# Atom_Multiout_Addon_Comp-Svid.net
KiCad netlist of a schematic drawn in EAGLE
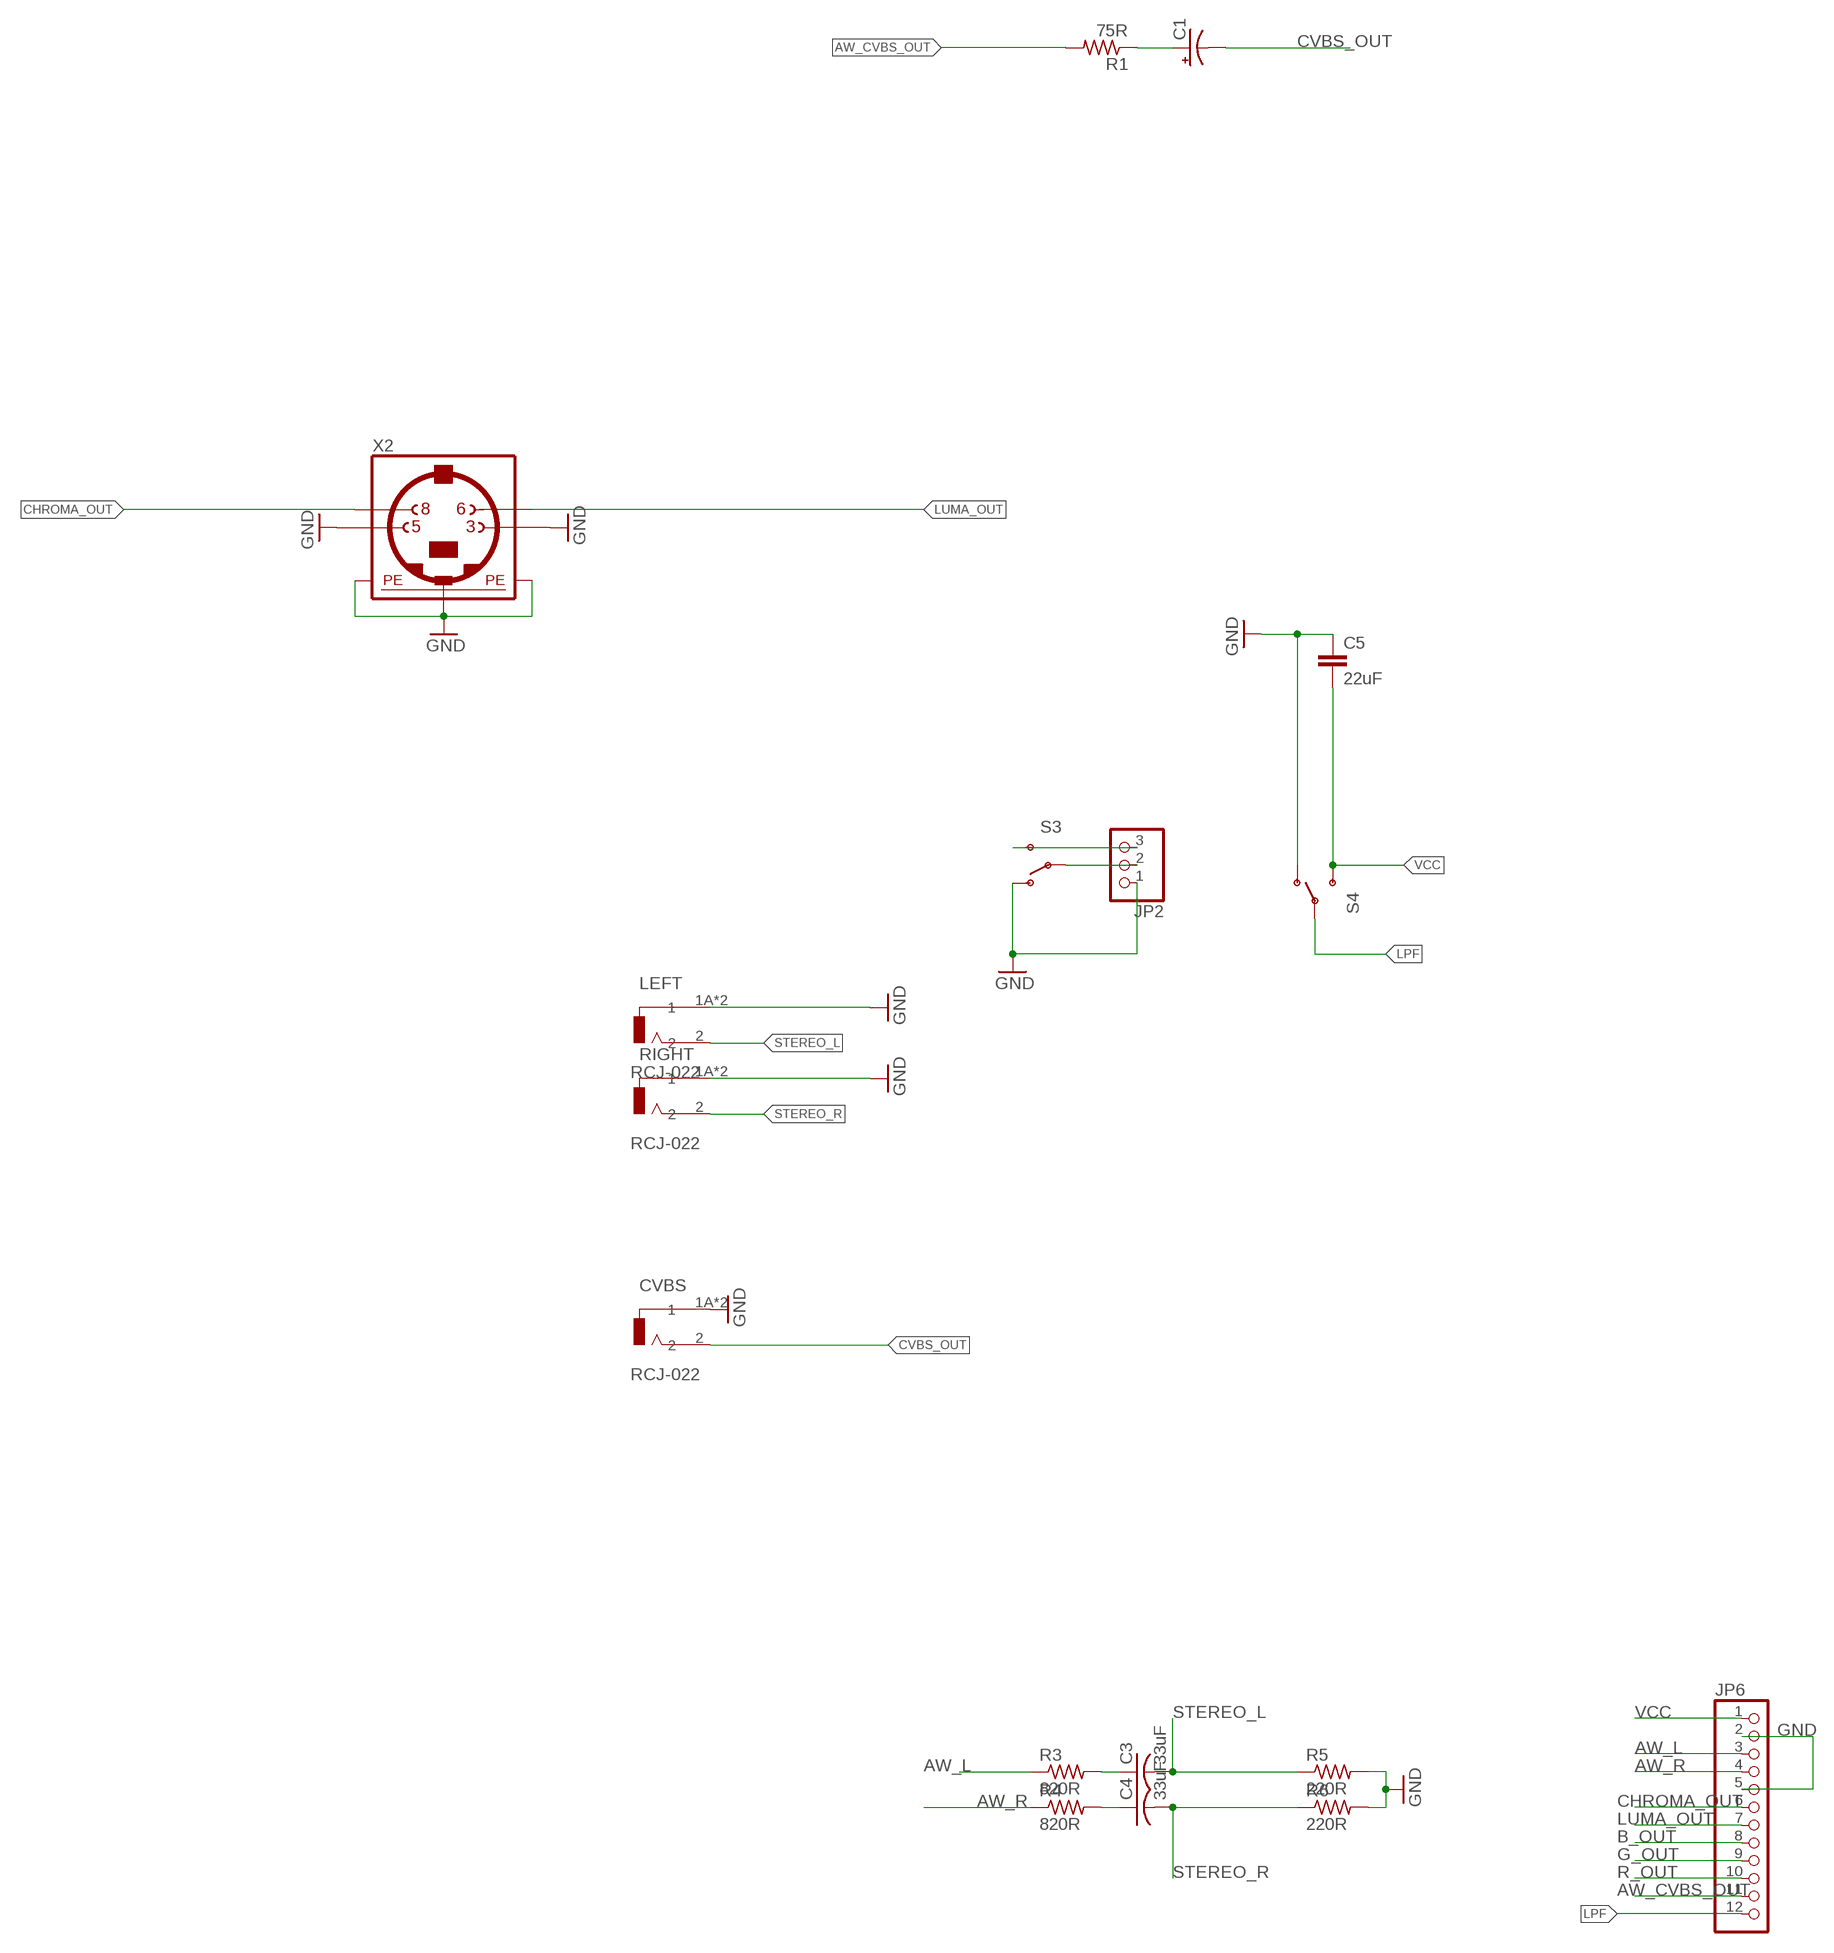
[diagram p0: schematic, sheet 1]

(export (version "E")
  (design (tool "Eeschema 10.0.6"))
  (components
    (comp (ref "C1")
      (value "CPOL-USD/7343-31W")
      (footprint "eagle-import:D_7343-31W")
      (libsource (lib "eagle-import") (part "CPOL-USD/7343-31W"))
    )
    (comp (ref "C3")
      (value "33uF")
      (footprint "eagle-import:C1206K")
      (libsource (lib "eagle-import") (part "C-USC1206K"))
    )
    (comp (ref "C4")
      (value "33uF")
      (footprint "eagle-import:C1206K")
      (libsource (lib "eagle-import") (part "C-USC1206K"))
    )
    (comp (ref "C5")
      (value "22uF")
      (footprint "eagle-import:C0603")
      (libsource (lib "eagle-import") (part "C-EUC0603"))
    )
    (comp (ref "CVBS")
      (value "RCJ-022")
      (footprint "eagle-import:CUI_RCJ-022")
      (fields (field (name "MF") "CUI Devices"))
      (libsource (lib "eagle-import") (part "RCJ-022"))
    )
    (comp (ref "JP2")
      (value "PINHD-1X03_2.54-S")
      (footprint "eagle-import:1X03-S")
      (libsource (lib "eagle-import") (part "PINHD-1X03_2.54-S"))
    )
    (comp (ref "JP6")
      (value "PINHD-1X12_2.54-S")
      (footprint "eagle-import:1X12-S")
      (libsource (lib "eagle-import") (part "PINHD-1X12_2.54-S"))
    )
    (comp (ref "LEFT")
      (value "RCJ-022")
      (footprint "eagle-import:CUI_RCJ-022")
      (fields (field (name "MF") "CUI Devices"))
      (libsource (lib "eagle-import") (part "RCJ-022"))
    )
    (comp (ref "R1")
      (value "75R")
      (footprint "eagle-import:R1206")
      (libsource (lib "eagle-import") (part "R-US_R1206"))
    )
    (comp (ref "R3")
      (value "820R")
      (footprint "eagle-import:R1206")
      (libsource (lib "eagle-import") (part "R-US_R1206"))
    )
    (comp (ref "R4")
      (value "820R")
      (footprint "eagle-import:R1206")
      (libsource (lib "eagle-import") (part "R-US_R1206"))
    )
    (comp (ref "R5")
      (value "220R")
      (footprint "eagle-import:R1206")
      (libsource (lib "eagle-import") (part "R-US_R1206"))
    )
    (comp (ref "R6")
      (value "220R")
      (footprint "eagle-import:R1206")
      (libsource (lib "eagle-import") (part "R-US_R1206"))
    )
    (comp (ref "RIGHT")
      (value "RCJ-022")
      (footprint "eagle-import:CUI_RCJ-022")
      (fields (field (name "MF") "CUI Devices"))
      (libsource (lib "eagle-import") (part "RCJ-022"))
    )
    (comp (ref "S3")
      (value "SWITCH-SPDT-SMD-A")
      (footprint "eagle-import:SWITCH-SPST-SMD-A")
      (libsource (lib "eagle-import") (part "SWITCH-SPDT-SMD-A"))
    )
    (comp (ref "S4")
      (value "SWITCH-SPDT-SMD-A")
      (footprint "eagle-import:SWITCH-SPST-SMD-A")
      (libsource (lib "eagle-import") (part "SWITCH-SPDT-SMD-A"))
    )
    (comp (ref "X2")
      (value "MINI_DIN_4")
      (footprint "eagle-import:M_DIN4")
      (libsource (lib "eagle-import") (part "MINI_DIN_4"))
    )
  )
  (nets
    (net (code "1") (name "/AW_L") (class "Default")
      (node (ref "JP6") (pin "3") (pinfunction "3_3") (pintype "passive"))
      (node (ref "R3") (pin "1") (pinfunction "1_1") (pintype "passive"))
    )
    (net (code "2") (name "/AW_R") (class "Default")
      (node (ref "JP6") (pin "4") (pinfunction "4_4") (pintype "passive"))
      (node (ref "R4") (pin "1") (pinfunction "1_1") (pintype "passive"))
    )
    (net (code "3") (name "/B_OUT") (class "Default")
      (node (ref "JP6") (pin "8") (pinfunction "8_8") (pintype "passive"))
    )
    (net (code "4") (name "/G_OUT") (class "Default")
      (node (ref "JP6") (pin "9") (pinfunction "9_9") (pintype "passive"))
    )
    (net (code "5") (name "/R_OUT") (class "Default")
      (node (ref "JP6") (pin "10") (pinfunction "10_10") (pintype "passive"))
    )
    (net (code "6") (name "AW_CVBS_OUT") (class "Default")
      (node (ref "JP6") (pin "11") (pinfunction "11_11") (pintype "passive"))
      (node (ref "R1") (pin "2") (pinfunction "2_2") (pintype "passive"))
    )
    (net (code "7") (name "CHROMA_OUT") (class "Default")
      (node (ref "JP6") (pin "6") (pinfunction "6_6") (pintype "passive"))
      (node (ref "X2") (pin "8") (pinfunction "8_8") (pintype "passive"))
    )
    (net (code "8") (name "CVBS_OUT") (class "Default")
      (node (ref "C1") (pin "-") (pinfunction "-_-") (pintype "passive"))
      (node (ref "CVBS") (pin "2") (pinfunction "2_2") (pintype "passive"))
    )
    (net (code "9") (name "GND") (class "Default")
      (node (ref "C5") (pin "1") (pinfunction "1_1") (pintype "passive"))
      (node (ref "CVBS") (pin "1A") (pinfunction "1_1A") (pintype "passive"))
      (node (ref "CVBS") (pin "1B") (pinfunction "1_1B") (pintype "passive"))
      (node (ref "JP2") (pin "1") (pinfunction "1_1") (pintype "passive"))
      (node (ref "JP6") (pin "2") (pinfunction "2_2") (pintype "passive"))
      (node (ref "JP6") (pin "5") (pinfunction "5_5") (pintype "passive"))
      (node (ref "LEFT") (pin "1A") (pinfunction "1_1A") (pintype "passive"))
      (node (ref "LEFT") (pin "1B") (pinfunction "1_1B") (pintype "passive"))
      (node (ref "R5") (pin "2") (pinfunction "2_2") (pintype "passive"))
      (node (ref "R6") (pin "2") (pinfunction "2_2") (pintype "passive"))
      (node (ref "RIGHT") (pin "1A") (pinfunction "1_1A") (pintype "passive"))
      (node (ref "RIGHT") (pin "1B") (pinfunction "1_1B") (pintype "passive"))
      (node (ref "S3") (pin "1") (pinfunction "O_1") (pintype "passive"))
      (node (ref "S4") (pin "1") (pinfunction "O_1") (pintype "passive"))
      (node (ref "X2") (pin "3") (pinfunction "3_3") (pintype "passive"))
      (node (ref "X2") (pin "5") (pinfunction "5_5") (pintype "passive"))
      (node (ref "X2") (pin "SH1") (pinfunction "PE1_SH1") (pintype "power_in"))
      (node (ref "X2") (pin "SH2") (pinfunction "PE2_SH2") (pintype "power_in"))
      (node (ref "X2") (pin "SH3") (pinfunction "PE3_SH3") (pintype "power_in"))
    )
    (net (code "10") (name "LPF") (class "Default")
      (node (ref "JP6") (pin "12") (pinfunction "12_12") (pintype "passive"))
      (node (ref "S4") (pin "2") (pinfunction "P_2") (pintype "passive"))
    )
    (net (code "11") (name "LUMA_OUT") (class "Default")
      (node (ref "JP6") (pin "7") (pinfunction "7_7") (pintype "passive"))
      (node (ref "X2") (pin "6") (pinfunction "6_6") (pintype "passive"))
    )
    (net (code "12") (name "Net-(C1-Pad+)") (class "Default")
      (node (ref "C1") (pin "+") (pinfunction "+_+") (pintype "passive"))
      (node (ref "R1") (pin "1") (pinfunction "1_1") (pintype "passive"))
    )
    (net (code "13") (name "Net-(C3-Pad1)") (class "Default")
      (node (ref "C3") (pin "1") (pinfunction "1_1") (pintype "passive"))
      (node (ref "R3") (pin "2") (pinfunction "2_2") (pintype "passive"))
    )
    (net (code "14") (name "Net-(C4-Pad1)") (class "Default")
      (node (ref "C4") (pin "1") (pinfunction "1_1") (pintype "passive"))
      (node (ref "R4") (pin "2") (pinfunction "2_2") (pintype "passive"))
    )
    (net (code "15") (name "Net-(S3-P)") (class "Default")
      (node (ref "JP2") (pin "2") (pinfunction "2_2") (pintype "passive"))
      (node (ref "S3") (pin "2") (pinfunction "P_2") (pintype "passive"))
    )
    (net (code "16") (name "Net-(S3-S)") (class "Default")
      (node (ref "JP2") (pin "3") (pinfunction "3_3") (pintype "passive"))
      (node (ref "S3") (pin "3") (pinfunction "S_3") (pintype "passive"))
    )
    (net (code "17") (name "STEREO_L") (class "Default")
      (node (ref "C3") (pin "2") (pinfunction "2_2") (pintype "passive"))
      (node (ref "LEFT") (pin "2") (pinfunction "2_2") (pintype "passive"))
      (node (ref "R5") (pin "1") (pinfunction "1_1") (pintype "passive"))
    )
    (net (code "18") (name "STEREO_R") (class "Default")
      (node (ref "C4") (pin "2") (pinfunction "2_2") (pintype "passive"))
      (node (ref "R6") (pin "1") (pinfunction "1_1") (pintype "passive"))
      (node (ref "RIGHT") (pin "2") (pinfunction "2_2") (pintype "passive"))
    )
    (net (code "19") (name "VCC") (class "Default")
      (node (ref "C5") (pin "2") (pinfunction "2_2") (pintype "passive"))
      (node (ref "JP6") (pin "1") (pinfunction "1_1") (pintype "passive"))
      (node (ref "S4") (pin "3") (pinfunction "S_3") (pintype "passive"))
    )
  )
)
